# room_controller2.net
KiCad netlist of a schematic drawn in EAGLE
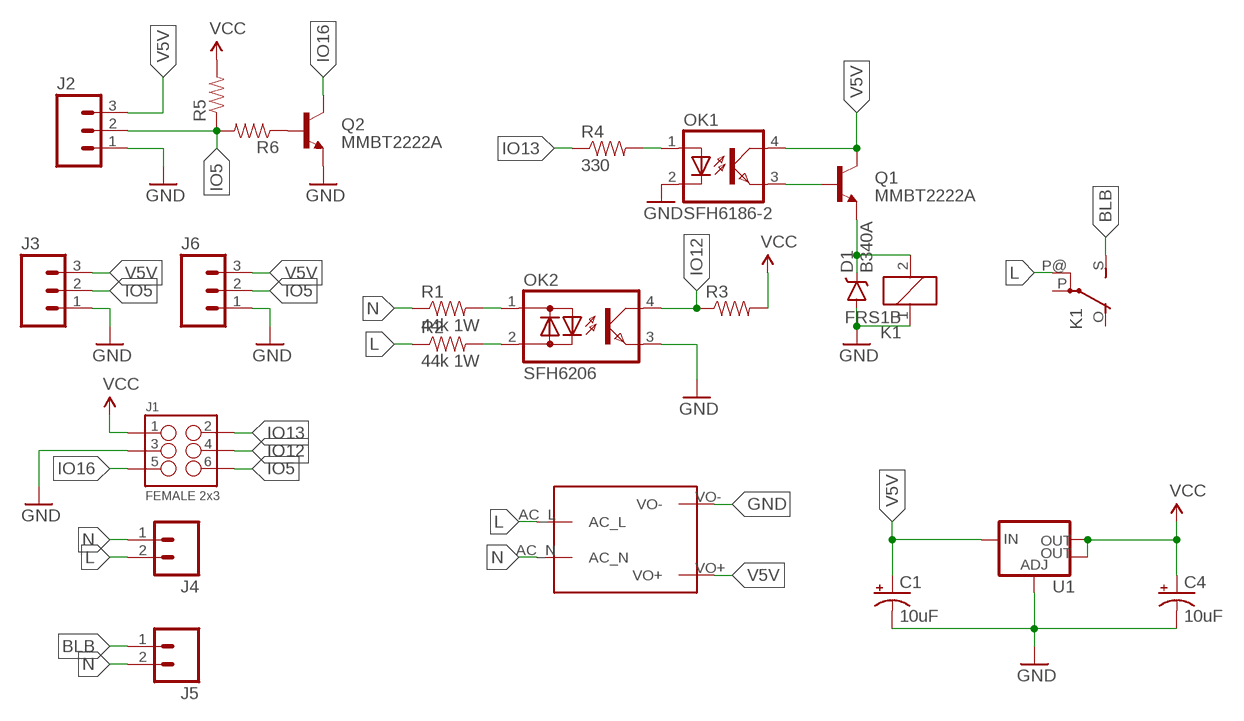
[diagram p0: schematic, sheet 1]

(export (version "E")
  (design (tool "Eeschema 10.0.6"))
  (components
    (comp (ref "C1")
      (value "10uF")
      (footprint "eagle-import:EIA3216-KIT")
      (libsource (lib "eagle-import") (part "CAP_POL1206-KIT"))
    )
    (comp (ref "C4")
      (value "10uF")
      (footprint "eagle-import:EIA3216-KIT")
      (libsource (lib "eagle-import") (part "CAP_POL1206-KIT"))
    )
    (comp (ref "D1")
      (value "B340A")
      (footprint "eagle-import:SMA-DIODE")
      (libsource (lib "eagle-import") (part "DIODE-SCHOTTKY-B340A"))
    )
    (comp (ref "J1")
      (value "FEMALE 2x3")
      (footprint "eagle-import:2X3-SHROUDED")
      (libsource (lib "eagle-import") (part "M03X2SHROUD"))
    )
    (comp (ref "J2")
      (value "M03PTH")
      (footprint "eagle-import:1X03")
      (libsource (lib "eagle-import") (part "M03PTH"))
    )
    (comp (ref "J3")
      (value "M03PTH")
      (footprint "eagle-import:1X03")
      (libsource (lib "eagle-import") (part "M03PTH"))
    )
    (comp (ref "J4")
      (value "M025MM")
      (footprint "eagle-import:SCREWTERMINAL-5MM-2")
      (libsource (lib "eagle-import") (part "M025MM"))
    )
    (comp (ref "J5")
      (value "M025MM")
      (footprint "eagle-import:SCREWTERMINAL-5MM-2")
      (libsource (lib "eagle-import") (part "M025MM"))
    )
    (comp (ref "J6")
      (value "M03PTH")
      (footprint "eagle-import:1X03")
      (libsource (lib "eagle-import") (part "M03PTH"))
    )
    (comp (ref "K1")
      (value "FRS1B")
      (footprint "eagle-import:FRS1B")
      (libsource (lib "eagle-import") (part "FRS1B"))
    )
    (comp (ref "OK1")
      (value "SFH6186-2")
      (footprint "eagle-import:SMD4")
      (libsource (lib "eagle-import") (part "SFH618?6-2"))
    )
    (comp (ref "OK2")
      (value "SFH6206")
      (footprint "eagle-import:DIL4-SMD")
      (libsource (lib "eagle-import") (part "SFH6206"))
    )
    (comp (ref "Q1")
      (value "MMBT2222A")
      (footprint "eagle-import:SOT23-3")
      (libsource (lib "eagle-import") (part "TRANSISTOR_NPNMMBT2222A"))
    )
    (comp (ref "Q2")
      (value "MMBT2222A")
      (footprint "eagle-import:SOT23-3")
      (libsource (lib "eagle-import") (part "TRANSISTOR_NPNMMBT2222A"))
    )
    (comp (ref "R1")
      (value "44k 1W")
      (footprint "eagle-import:AXIAL-0.4")
      (libsource (lib "eagle-import") (part "SparkFun-Resistors_RESISTORPTH-1/4W"))
    )
    (comp (ref "R2")
      (value "44k 1W")
      (footprint "eagle-import:AXIAL-0.4")
      (libsource (lib "eagle-import") (part "SparkFun-Resistors_RESISTORPTH-1/4W"))
    )
    (comp (ref "R3")
      (value "RESISTOR0805-RES")
      (footprint "eagle-import:0805")
      (libsource (lib "eagle-import") (part "RESISTOR0805-RES"))
    )
    (comp (ref "R4")
      (value "330")
      (footprint "eagle-import:0805")
      (libsource (lib "eagle-import") (part "RESISTOR0805-RES"))
    )
    (comp (ref "R5")
      (value "RESISTOR0805-RES")
      (footprint "eagle-import:0805")
      (libsource (lib "eagle-import") (part "RESISTOR0805-RES"))
    )
    (comp (ref "R6")
      (value "RESISTOR0805-RES")
      (footprint "eagle-import:0805")
      (libsource (lib "eagle-import") (part "RESISTOR0805-RES"))
    )
    (comp (ref "U$1")
      (value "MAINS_CONVERTERS")
      (footprint "eagle-import:HLK-PM01")
      (libsource (lib "eagle-import") (part "MAINS_CONVERTERS"))
    )
    (comp (ref "U1")
      (value "V_REG_LM1117SOT223")
      (footprint "eagle-import:SOT223")
      (libsource (lib "eagle-import") (part "V_REG_LM1117SOT223"))
    )
  )
  (nets
    (net (code "1") (name "BLB") (class "Default")
      (node (ref "J5") (pin "1") (pinfunction "1_1") (pintype "passive"))
      (node (ref "K1") (pin "S") (pinfunction "S_S") (pintype "passive"))
    )
    (net (code "2") (name "GND") (class "Default")
      (node (ref "C1") (pin "C") (pinfunction "-_C") (pintype "passive"))
      (node (ref "C4") (pin "C") (pinfunction "-_C") (pintype "passive"))
      (node (ref "D1") (pin "A") (pinfunction "A_A") (pintype "passive"))
      (node (ref "J1") (pin "3") (pinfunction "3_3") (pintype "bidirectional"))
      (node (ref "J2") (pin "1") (pinfunction "1_1") (pintype "passive"))
      (node (ref "J3") (pin "1") (pinfunction "1_1") (pintype "passive"))
      (node (ref "J6") (pin "1") (pinfunction "1_1") (pintype "passive"))
      (node (ref "K1") (pin "1") (pinfunction "1_1") (pintype "passive"))
      (node (ref "OK1") (pin "2") (pinfunction "C_2") (pintype "passive"))
      (node (ref "OK2") (pin "3") (pinfunction "E_3") (pintype "passive"))
      (node (ref "Q2") (pin "2") (pinfunction "E_2") (pintype "passive"))
      (node (ref "U$1") (pin "VO-") (pinfunction "VO-_VO-") (pintype "output"))
      (node (ref "U1") (pin "1") (pinfunction "ADJ_1") (pintype "input"))
    )
    (net (code "3") (name "IO5") (class "Default")
      (node (ref "J1") (pin "6") (pinfunction "6_6") (pintype "bidirectional"))
      (node (ref "J2") (pin "2") (pinfunction "2_2") (pintype "passive"))
      (node (ref "J3") (pin "2") (pinfunction "2_2") (pintype "passive"))
      (node (ref "J6") (pin "2") (pinfunction "2_2") (pintype "passive"))
      (node (ref "R5") (pin "1") (pinfunction "1_1") (pintype "passive"))
      (node (ref "R6") (pin "2") (pinfunction "2_2") (pintype "passive"))
    )
    (net (code "4") (name "IO12") (class "Default")
      (node (ref "J1") (pin "4") (pinfunction "4_4") (pintype "bidirectional"))
      (node (ref "OK2") (pin "4") (pinfunction "C_4") (pintype "passive"))
      (node (ref "R3") (pin "1") (pinfunction "1_1") (pintype "passive"))
    )
    (net (code "5") (name "IO13") (class "Default")
      (node (ref "J1") (pin "2") (pinfunction "2_2") (pintype "bidirectional"))
      (node (ref "R4") (pin "1") (pinfunction "1_1") (pintype "passive"))
    )
    (net (code "6") (name "IO16") (class "Default")
      (node (ref "J1") (pin "5") (pinfunction "5_5") (pintype "bidirectional"))
      (node (ref "Q2") (pin "3") (pinfunction "C_3") (pintype "passive"))
    )
    (net (code "7") (name "L") (class "Default")
      (node (ref "J4") (pin "2") (pinfunction "2_2") (pintype "passive"))
      (node (ref "K1") (pin "P@") (pinfunction "P_P@") (pintype "passive"))
      (node (ref "R2") (pin "P$1") (pinfunction "1_P$1") (pintype "passive"))
      (node (ref "U$1") (pin "AC_L") (pinfunction "AC_L_AC_L") (pintype "input"))
    )
    (net (code "8") (name "N") (class "Default")
      (node (ref "J4") (pin "1") (pinfunction "1_1") (pintype "passive"))
      (node (ref "J5") (pin "2") (pinfunction "2_2") (pintype "passive"))
      (node (ref "R1") (pin "P$1") (pinfunction "1_P$1") (pintype "passive"))
      (node (ref "U$1") (pin "AC_N") (pinfunction "AC_N_AC_N") (pintype "input"))
    )
    (net (code "9") (name "Net-(OK1-A)") (class "Default")
      (node (ref "OK1") (pin "1") (pinfunction "A_1") (pintype "passive"))
      (node (ref "R4") (pin "2") (pinfunction "2_2") (pintype "passive"))
    )
    (net (code "10") (name "Net-(OK1-EMIT)") (class "Default")
      (node (ref "OK1") (pin "3") (pinfunction "EMIT_3") (pintype "passive"))
      (node (ref "Q1") (pin "1") (pinfunction "B_1") (pintype "passive"))
    )
    (net (code "11") (name "Net-(OK2-AC1)") (class "Default")
      (node (ref "OK2") (pin "1") (pinfunction "AC1_1") (pintype "passive"))
      (node (ref "R1") (pin "P$2") (pinfunction "2_P$2") (pintype "passive"))
    )
    (net (code "12") (name "Net-(OK2-AC2)") (class "Default")
      (node (ref "OK2") (pin "2") (pinfunction "AC2_2") (pintype "passive"))
      (node (ref "R2") (pin "P$2") (pinfunction "2_P$2") (pintype "passive"))
    )
    (net (code "13") (name "Net-(Q1-E)") (class "Default")
      (node (ref "D1") (pin "C") (pinfunction "C_C") (pintype "passive"))
      (node (ref "K1") (pin "2") (pinfunction "2_2") (pintype "passive"))
      (node (ref "Q1") (pin "2") (pinfunction "E_2") (pintype "passive"))
    )
    (net (code "14") (name "Net-(Q2-B)") (class "Default")
      (node (ref "Q2") (pin "1") (pinfunction "B_1") (pintype "passive"))
      (node (ref "R6") (pin "1") (pinfunction "1_1") (pintype "passive"))
    )
    (net (code "15") (name "V5V") (class "Default")
      (node (ref "C1") (pin "A") (pinfunction "+_A") (pintype "passive"))
      (node (ref "J2") (pin "3") (pinfunction "3_3") (pintype "passive"))
      (node (ref "J3") (pin "3") (pinfunction "3_3") (pintype "passive"))
      (node (ref "J6") (pin "3") (pinfunction "3_3") (pintype "passive"))
      (node (ref "OK1") (pin "4") (pinfunction "COL_4") (pintype "passive"))
      (node (ref "Q1") (pin "3") (pinfunction "C_3") (pintype "passive"))
      (node (ref "U$1") (pin "VO+") (pinfunction "VO+_VO+") (pintype "output"))
      (node (ref "U1") (pin "3") (pinfunction "IN_3") (pintype "input"))
    )
    (net (code "16") (name "VCC") (class "Default")
      (node (ref "C4") (pin "A") (pinfunction "+_A") (pintype "passive"))
      (node (ref "J1") (pin "1") (pinfunction "1_1") (pintype "bidirectional"))
      (node (ref "R3") (pin "2") (pinfunction "2_2") (pintype "passive"))
      (node (ref "R5") (pin "2") (pinfunction "2_2") (pintype "passive"))
      (node (ref "U1") (pin "2") (pinfunction "OUT_2") (pintype "output"))
      (node (ref "U1") (pin "4") (pinfunction "OUT_4") (pintype "output"))
    )
    (net (code "17") (name "unconnected-(K1-PadO)") (class "Default")
      (node (ref "K1") (pin "O") (pinfunction "O_O") (pintype "passive"))
    )
    (net (code "18") (name "unconnected-(K1-PadP)") (class "Default")
      (node (ref "K1") (pin "P") (pinfunction "P_P") (pintype "passive"))
    )
  )
)
